# MotorControl.net
KiCad netlist of a schematic drawn in Altium Designer
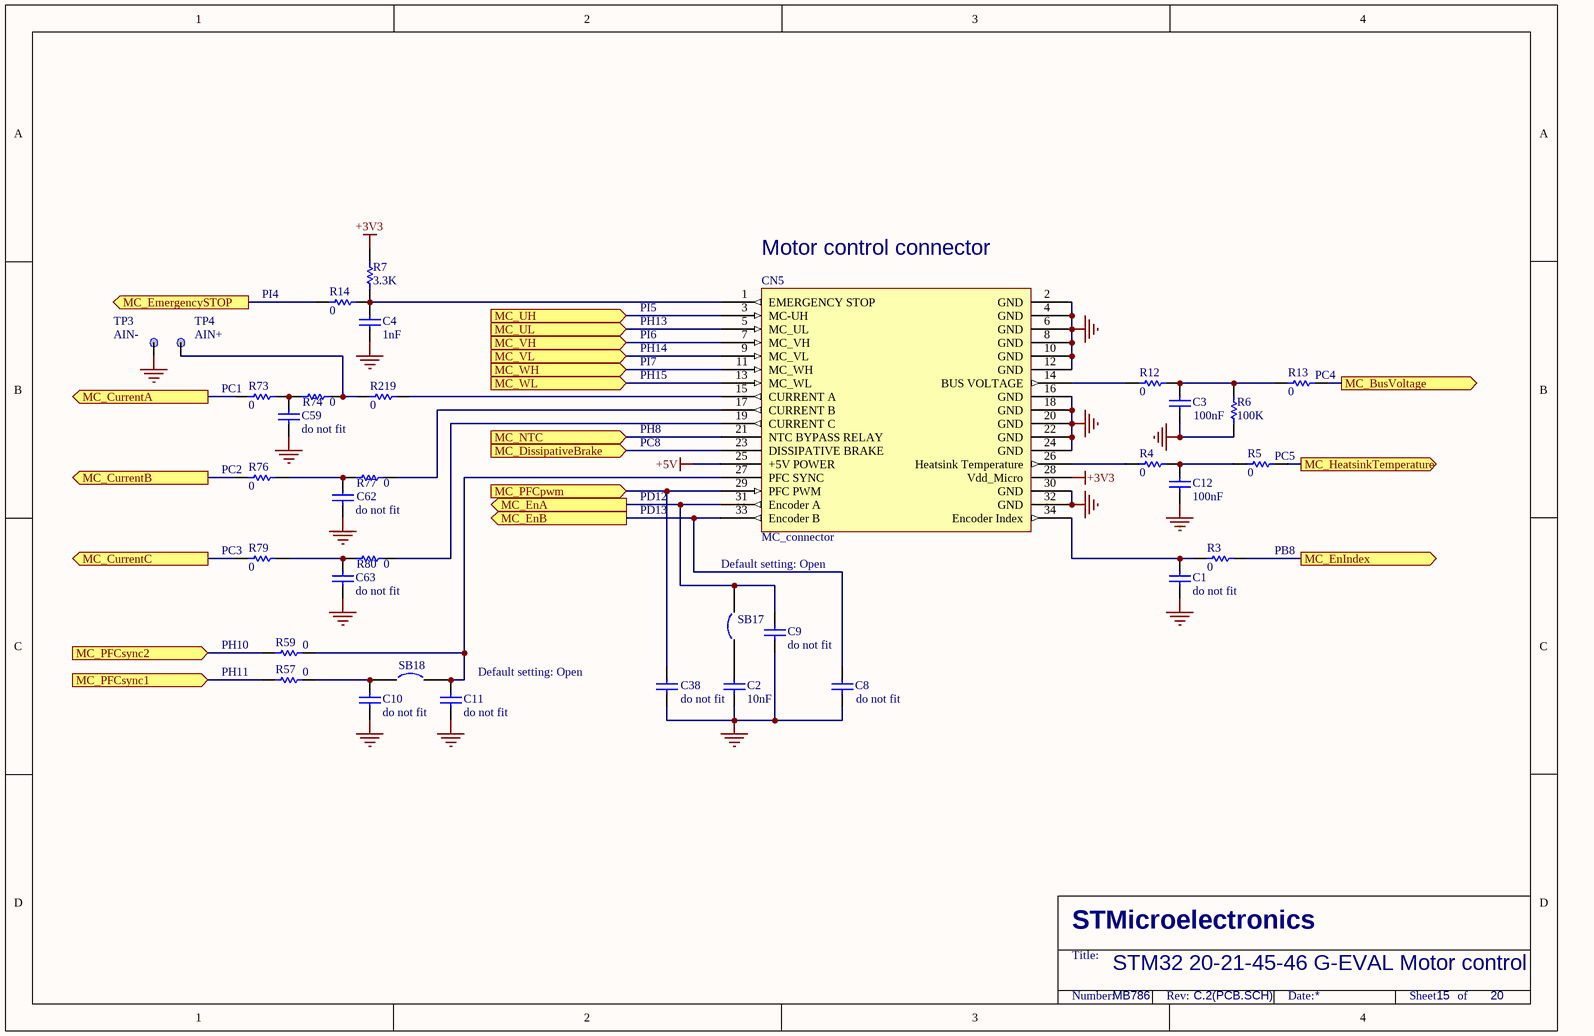
[diagram p0: MotorControl.SchDoc]

(export (version "E")
  (design (tool "Eeschema 10.0.6"))
  (components
    (comp (ref "C1")
      (value "do not fit")
      (footprint "0603C")
      (description "Capacitor")
      (fields (field (name "PUBLISHER") "Altium Limited"))
      (libsource (lib "Miscellaneous Devices") (part "cap"))
    )
    (comp (ref "C2")
      (value "10nF")
      (footprint "0402C")
      (description "Capacitor")
      (fields (field (name "PUBLISHER") "Altium Limited"))
      (libsource (lib "Miscellaneous Devices") (part "cap"))
    )
    (comp (ref "C3")
      (value "100nF")
      (footprint "0402C")
      (description "Capacitor")
      (fields (field (name "PUBLISHER") "Altium Limited"))
      (libsource (lib "Miscellaneous Devices") (part "cap"))
    )
    (comp (ref "C4")
      (value "1nF")
      (footprint "0603C")
      (description "Capacitor")
      (fields (field (name "PUBLISHER") "Altium Limited"))
      (libsource (lib "Miscellaneous Devices") (part "CAP"))
    )
    (comp (ref "C8")
      (value "do not fit")
      (footprint "0603C")
      (description "Capacitor")
      (fields (field (name "PUBLISHER") "Altium Limited"))
      (libsource (lib "Miscellaneous Devices") (part "cap"))
    )
    (comp (ref "C9")
      (value "do not fit")
      (footprint "0603C")
      (description "Capacitor")
      (fields (field (name "PUBLISHER") "Altium Limited"))
      (libsource (lib "Miscellaneous Devices") (part "cap"))
    )
    (comp (ref "C10")
      (value "do not fit")
      (footprint "0603C")
      (description "Capacitor")
      (fields (field (name "PUBLISHER") "Altium Limited"))
      (libsource (lib "Miscellaneous Devices") (part "cap"))
    )
    (comp (ref "C11")
      (value "do not fit")
      (footprint "0603C")
      (description "Capacitor")
      (fields (field (name "PUBLISHER") "Altium Limited"))
      (libsource (lib "Miscellaneous Devices") (part "cap"))
    )
    (comp (ref "C12")
      (value "100nF")
      (footprint "0402C")
      (description "Capacitor")
      (fields (field (name "PUBLISHER") "Altium Limited"))
      (libsource (lib "Miscellaneous Devices") (part "cap"))
    )
    (comp (ref "C38")
      (value "do not fit")
      (footprint "0603C")
      (description "Capacitor")
      (fields (field (name "PUBLISHER") "Altium Limited"))
      (libsource (lib "Miscellaneous Devices") (part "cap"))
    )
    (comp (ref "C59")
      (value "do not fit")
      (footprint "0603C")
      (description "Capacitor")
      (fields (field (name "PUBLISHER") "Altium Limited"))
      (libsource (lib "Miscellaneous Devices") (part "cap"))
    )
    (comp (ref "C62")
      (value "do not fit")
      (footprint "0603C")
      (description "Capacitor")
      (fields (field (name "PUBLISHER") "Altium Limited"))
      (libsource (lib "Miscellaneous Devices") (part "cap"))
    )
    (comp (ref "C63")
      (value "do not fit")
      (footprint "0603C")
      (description "Capacitor")
      (fields (field (name "PUBLISHER") "Altium Limited"))
      (libsource (lib "Miscellaneous Devices") (part "cap"))
    )
    (comp (ref "CN5")
      (value "MC_connector")
      (footprint "IDC34S")
      (libsource (lib "MB525") (part "MC_connector"))
    )
    (comp (ref "R3")
      (value "0")
      (footprint "0603R")
      (description "Resistor")
      (fields (field (name "PUBLISHER") "Altium Limited"))
      (libsource (lib "Miscellaneous Devices") (part "Res1"))
    )
    (comp (ref "R4")
      (value "0")
      (footprint "0603R")
      (description "Resistor")
      (fields (field (name "PUBLISHER") "Altium Limited"))
      (libsource (lib "Miscellaneous Devices") (part "Res1"))
    )
    (comp (ref "R5")
      (value "0")
      (footprint "0603R")
      (description "Resistor")
      (fields (field (name "PUBLISHER") "Altium Limited"))
      (libsource (lib "Miscellaneous Devices") (part "Res1"))
    )
    (comp (ref "R6")
      (value "100K")
      (footprint "0402R")
      (description "Resistor")
      (fields (field (name "PUBLISHER") "Altium Limited"))
      (libsource (lib "Miscellaneous Devices") (part "Res1"))
    )
    (comp (ref "R7")
      (value "3.3K")
      (footprint "0603R")
      (description "Resistor")
      (fields (field (name "PUBLISHER") "Altium Limited"))
      (libsource (lib "Miscellaneous Devices") (part "Res1"))
    )
    (comp (ref "R12")
      (value "0")
      (footprint "0603R")
      (description "Resistor")
      (fields (field (name "PUBLISHER") "Altium Limited"))
      (libsource (lib "Miscellaneous Devices") (part "Res1"))
    )
    (comp (ref "R13")
      (value "0")
      (footprint "0603R")
      (description "Resistor")
      (fields (field (name "PUBLISHER") "Altium Limited"))
      (libsource (lib "Miscellaneous Devices") (part "Res1"))
    )
    (comp (ref "R14")
      (value "0")
      (footprint "0603R")
      (description "Resistor")
      (fields (field (name "PUBLISHER") "Altium Limited"))
      (libsource (lib "Miscellaneous Devices") (part "Res1"))
    )
    (comp (ref "R57")
      (value "0")
      (footprint "0603R")
      (description "Resistor")
      (fields (field (name "PUBLISHER") "Altium Limited"))
      (libsource (lib "Miscellaneous Devices") (part "Res1"))
    )
    (comp (ref "R59")
      (value "0")
      (footprint "0603R")
      (description "Resistor")
      (fields (field (name "PUBLISHER") "Altium Limited"))
      (libsource (lib "Miscellaneous Devices") (part "Res1"))
    )
    (comp (ref "R73")
      (value "0")
      (footprint "0603R")
      (description "Resistor")
      (fields (field (name "PUBLISHER") "Altium Limited"))
      (libsource (lib "Miscellaneous Devices") (part "Res1"))
    )
    (comp (ref "R74")
      (value "0")
      (footprint "0603R")
      (description "Resistor")
      (fields (field (name "PUBLISHER") "Altium Limited"))
      (libsource (lib "Miscellaneous Devices") (part "Res1"))
    )
    (comp (ref "R76")
      (value "0")
      (footprint "0603R")
      (description "Resistor")
      (fields (field (name "PUBLISHER") "Altium Limited"))
      (libsource (lib "Miscellaneous Devices") (part "Res1"))
    )
    (comp (ref "R77")
      (value "0")
      (footprint "0603R")
      (description "Resistor")
      (fields (field (name "PUBLISHER") "Altium Limited"))
      (libsource (lib "Miscellaneous Devices") (part "Res1"))
    )
    (comp (ref "R79")
      (value "0")
      (footprint "0603R")
      (description "Resistor")
      (fields (field (name "PUBLISHER") "Altium Limited"))
      (libsource (lib "Miscellaneous Devices") (part "Res1"))
    )
    (comp (ref "R80")
      (value "0")
      (footprint "0603R")
      (description "Resistor")
      (fields (field (name "PUBLISHER") "Altium Limited"))
      (libsource (lib "Miscellaneous Devices") (part "Res1"))
    )
    (comp (ref "R219")
      (value "0")
      (footprint "0603R")
      (description "Resistor")
      (fields (field (name "PUBLISHER") "Altium Limited"))
      (libsource (lib "Miscellaneous Devices") (part "Res1"))
    )
    (comp (ref "SB17")
      (value "~")
      (footprint "JP2_SMD")
      (description "Circuit Breaker")
      (fields (field (name "PUBLISHER") "Altium Limited"))
      (libsource (lib "Miscellaneous Devices") (part "Circuit Breaker"))
    )
    (comp (ref "SB18")
      (value "~")
      (footprint "JP2_SMD")
      (description "Circuit Breaker")
      (fields (field (name "PUBLISHER") "Altium Limited"))
      (libsource (lib "Miscellaneous Devices") (part "Circuit Breaker"))
    )
    (comp (ref "TP3") (value "AIN-") (footprint "TP") (libsource (lib "*") (part "TP")))
    (comp (ref "TP4") (value "AIN+") (footprint "TP") (libsource (lib "*") (part "TP")))
  )
  (nets
    (net (code "1") (name "+3V3") (class "Default")
      (node (ref "CN5") (pin "28") (pinfunction "Vdd_Micro_28") (pintype "power_in"))
      (node (ref "R7") (pin "2") (pinfunction "2_2") (pintype "passive"))
    )
    (net (code "2") (name "+5V") (class "Default")
      (node (ref "CN5") (pin "25") (pinfunction "+5V_POWER_25") (pintype "power_in"))
    )
    (net (code "3") (name "/MC_BusVoltage") (class "Default")
      (node (ref "R13") (pin "2") (pinfunction "2_2") (pintype "passive"))
    )
    (net (code "4") (name "/MC_CurrentA") (class "Default")
      (node (ref "R73") (pin "1") (pinfunction "1_1") (pintype "passive"))
    )
    (net (code "5") (name "/MC_CurrentB") (class "Default")
      (node (ref "R76") (pin "1") (pinfunction "1_1") (pintype "passive"))
    )
    (net (code "6") (name "/MC_CurrentC") (class "Default")
      (node (ref "R79") (pin "1") (pinfunction "1_1") (pintype "passive"))
    )
    (net (code "7") (name "/MC_DissipativeBrake") (class "Default")
      (node (ref "CN5") (pin "23") (pinfunction "DISSIPATIVE_BRAKE_23") (pintype "passive"))
    )
    (net (code "8") (name "/MC_EmergencySTOP") (class "Default")
      (node (ref "R14") (pin "2") (pinfunction "2_2") (pintype "passive"))
    )
    (net (code "9") (name "/MC_EnA") (class "Default")
      (node (ref "C9") (pin "2") (pinfunction "2_2") (pintype "passive"))
      (node (ref "CN5") (pin "31") (pinfunction "Encoder_A_31") (pintype "output"))
      (node (ref "SB17") (pin "2") (pinfunction "2_2") (pintype "passive"))
    )
    (net (code "10") (name "/MC_EnB") (class "Default")
      (node (ref "C8") (pin "2") (pinfunction "2_2") (pintype "passive"))
      (node (ref "CN5") (pin "33") (pinfunction "Encoder_B_33") (pintype "output"))
    )
    (net (code "11") (name "/MC_EnIndex") (class "Default")
      (node (ref "R3") (pin "2") (pinfunction "2_2") (pintype "passive"))
    )
    (net (code "12") (name "/MC_HeatsinkTemperature") (class "Default")
      (node (ref "R5") (pin "2") (pinfunction "2_2") (pintype "passive"))
    )
    (net (code "13") (name "/MC_NTC") (class "Default")
      (node (ref "CN5") (pin "21") (pinfunction "NTC_BYPASS_RELAY_21") (pintype "passive"))
    )
    (net (code "14") (name "/MC_PFCpwm") (class "Default")
      (node (ref "C38") (pin "2") (pinfunction "2_2") (pintype "passive"))
      (node (ref "CN5") (pin "29") (pinfunction "PFC_PWM_29") (pintype "input"))
    )
    (net (code "15") (name "/MC_PFCsync1") (class "Default")
      (node (ref "R57") (pin "1") (pinfunction "1_1") (pintype "passive"))
    )
    (net (code "16") (name "/MC_PFCsync2") (class "Default")
      (node (ref "R59") (pin "1") (pinfunction "1_1") (pintype "passive"))
    )
    (net (code "17") (name "/MC_UH") (class "Default")
      (node (ref "CN5") (pin "3") (pinfunction "MC-UH_3") (pintype "input"))
    )
    (net (code "18") (name "/MC_UL") (class "Default")
      (node (ref "CN5") (pin "5") (pinfunction "MC_UL_5") (pintype "input"))
    )
    (net (code "19") (name "/MC_VH") (class "Default")
      (node (ref "CN5") (pin "7") (pinfunction "MC_VH_7") (pintype "input"))
    )
    (net (code "20") (name "/MC_VL") (class "Default")
      (node (ref "CN5") (pin "9") (pinfunction "MC_VL_9") (pintype "input"))
    )
    (net (code "21") (name "/MC_WH") (class "Default")
      (node (ref "CN5") (pin "11") (pinfunction "MC_WH_11") (pintype "input"))
    )
    (net (code "22") (name "/MC_WL") (class "Default")
      (node (ref "CN5") (pin "13") (pinfunction "MC_WL_13") (pintype "input"))
    )
    (net (code "23") (name "GND") (class "Default")
      (node (ref "C1") (pin "1") (pinfunction "1_1") (pintype "passive"))
      (node (ref "C10") (pin "1") (pinfunction "1_1") (pintype "passive"))
      (node (ref "C11") (pin "1") (pinfunction "1_1") (pintype "passive"))
      (node (ref "C12") (pin "1") (pinfunction "1_1") (pintype "passive"))
      (node (ref "C2") (pin "1") (pinfunction "1_1") (pintype "passive"))
      (node (ref "C3") (pin "1") (pinfunction "1_1") (pintype "passive"))
      (node (ref "C38") (pin "1") (pinfunction "1_1") (pintype "passive"))
      (node (ref "C4") (pin "1") (pinfunction "1_1") (pintype "passive"))
      (node (ref "C59") (pin "1") (pinfunction "1_1") (pintype "passive"))
      (node (ref "C62") (pin "1") (pinfunction "1_1") (pintype "passive"))
      (node (ref "C63") (pin "1") (pinfunction "1_1") (pintype "passive"))
      (node (ref "C8") (pin "1") (pinfunction "1_1") (pintype "passive"))
      (node (ref "C9") (pin "1") (pinfunction "1_1") (pintype "passive"))
      (node (ref "CN5") (pin "10") (pinfunction "GND_10") (pintype "power_in"))
      (node (ref "CN5") (pin "12") (pinfunction "GND_12") (pintype "power_in"))
      (node (ref "CN5") (pin "16") (pinfunction "GND_16") (pintype "power_in"))
      (node (ref "CN5") (pin "18") (pinfunction "GND_18") (pintype "power_in"))
      (node (ref "CN5") (pin "2") (pinfunction "GND_2") (pintype "power_in"))
      (node (ref "CN5") (pin "20") (pinfunction "GND_20") (pintype "power_in"))
      (node (ref "CN5") (pin "22") (pinfunction "GND_22") (pintype "power_in"))
      (node (ref "CN5") (pin "24") (pinfunction "GND_24") (pintype "power_in"))
      (node (ref "CN5") (pin "30") (pinfunction "GND_30") (pintype "power_in"))
      (node (ref "CN5") (pin "32") (pinfunction "GND_32") (pintype "power_in"))
      (node (ref "CN5") (pin "4") (pinfunction "GND_4") (pintype "power_in"))
      (node (ref "CN5") (pin "6") (pinfunction "GND_6") (pintype "power_in"))
      (node (ref "CN5") (pin "8") (pinfunction "GND_8") (pintype "power_in"))
      (node (ref "R6") (pin "1") (pinfunction "1_1") (pintype "passive"))
      (node (ref "TP3") (pin "1") (pinfunction "1_1") (pintype "passive"))
    )
    (net (code "24") (name "Net-(C2-Pad2)") (class "Default")
      (node (ref "C2") (pin "2") (pinfunction "2_2") (pintype "passive"))
      (node (ref "SB17") (pin "1") (pinfunction "1_1") (pintype "passive"))
    )
    (net (code "25") (name "Net-(C3-Pad2)") (class "Default")
      (node (ref "C3") (pin "2") (pinfunction "2_2") (pintype "passive"))
      (node (ref "R12") (pin "2") (pinfunction "2_2") (pintype "passive"))
      (node (ref "R13") (pin "1") (pinfunction "1_1") (pintype "passive"))
      (node (ref "R6") (pin "2") (pinfunction "2_2") (pintype "passive"))
    )
    (net (code "26") (name "Net-(C10-Pad2)") (class "Default")
      (node (ref "C10") (pin "2") (pinfunction "2_2") (pintype "passive"))
      (node (ref "R57") (pin "2") (pinfunction "2_2") (pintype "passive"))
      (node (ref "SB18") (pin "1") (pinfunction "1_1") (pintype "passive"))
    )
    (net (code "27") (name "Net-(C12-Pad2)") (class "Default")
      (node (ref "C12") (pin "2") (pinfunction "2_2") (pintype "passive"))
      (node (ref "R4") (pin "2") (pinfunction "2_2") (pintype "passive"))
      (node (ref "R5") (pin "1") (pinfunction "1_1") (pintype "passive"))
    )
    (net (code "28") (name "Net-(C59-Pad2)") (class "Default")
      (node (ref "C59") (pin "2") (pinfunction "2_2") (pintype "passive"))
      (node (ref "R73") (pin "2") (pinfunction "2_2") (pintype "passive"))
      (node (ref "R74") (pin "1") (pinfunction "1_1") (pintype "passive"))
    )
    (net (code "29") (name "Net-(C62-Pad2)") (class "Default")
      (node (ref "C62") (pin "2") (pinfunction "2_2") (pintype "passive"))
      (node (ref "R76") (pin "2") (pinfunction "2_2") (pintype "passive"))
      (node (ref "R77") (pin "1") (pinfunction "1_1") (pintype "passive"))
    )
    (net (code "30") (name "Net-(C63-Pad2)") (class "Default")
      (node (ref "C63") (pin "2") (pinfunction "2_2") (pintype "passive"))
      (node (ref "R79") (pin "2") (pinfunction "2_2") (pintype "passive"))
      (node (ref "R80") (pin "1") (pinfunction "1_1") (pintype "passive"))
    )
    (net (code "31") (name "Net-(CN5-BUS_VOLTAGE)") (class "Default")
      (node (ref "CN5") (pin "14") (pinfunction "BUS_VOLTAGE_14") (pintype "output"))
      (node (ref "R12") (pin "1") (pinfunction "1_1") (pintype "passive"))
    )
    (net (code "32") (name "Net-(CN5-CURRENT_A)") (class "Default")
      (node (ref "CN5") (pin "15") (pinfunction "CURRENT_A_15") (pintype "output"))
      (node (ref "R219") (pin "1") (pinfunction "1_1") (pintype "passive"))
    )
    (net (code "33") (name "Net-(CN5-CURRENT_B)") (class "Default")
      (node (ref "CN5") (pin "17") (pinfunction "CURRENT_B_17") (pintype "output"))
      (node (ref "R77") (pin "2") (pinfunction "2_2") (pintype "passive"))
    )
    (net (code "34") (name "Net-(CN5-CURRENT_C)") (class "Default")
      (node (ref "CN5") (pin "19") (pinfunction "CURRENT_C_19") (pintype "output"))
      (node (ref "R80") (pin "2") (pinfunction "2_2") (pintype "passive"))
    )
    (net (code "35") (name "Net-(CN5-EMERGENCY_STOP)") (class "Default")
      (node (ref "C4") (pin "2") (pinfunction "2_2") (pintype "passive"))
      (node (ref "CN5") (pin "1") (pinfunction "EMERGENCY_STOP_1") (pintype "output"))
      (node (ref "R14") (pin "1") (pinfunction "1_1") (pintype "passive"))
      (node (ref "R7") (pin "1") (pinfunction "1_1") (pintype "passive"))
    )
    (net (code "36") (name "Net-(CN5-Encoder_Index)") (class "Default")
      (node (ref "C1") (pin "2") (pinfunction "2_2") (pintype "passive"))
      (node (ref "CN5") (pin "34") (pinfunction "Encoder_Index_34") (pintype "output"))
      (node (ref "R3") (pin "1") (pinfunction "1_1") (pintype "passive"))
    )
    (net (code "37") (name "Net-(CN5-Heatsink_Temperature)") (class "Default")
      (node (ref "CN5") (pin "26") (pinfunction "Heatsink_Temperature_26") (pintype "output"))
      (node (ref "R4") (pin "1") (pinfunction "1_1") (pintype "passive"))
    )
    (net (code "38") (name "Net-(CN5-PFC_SYNC)") (class "Default")
      (node (ref "C11") (pin "2") (pinfunction "2_2") (pintype "passive"))
      (node (ref "CN5") (pin "27") (pinfunction "PFC_SYNC_27") (pintype "passive"))
      (node (ref "R59") (pin "2") (pinfunction "2_2") (pintype "passive"))
      (node (ref "SB18") (pin "2") (pinfunction "2_2") (pintype "passive"))
    )
    (net (code "39") (name "Net-(R219-Pad2)") (class "Default")
      (node (ref "R219") (pin "2") (pinfunction "2_2") (pintype "passive"))
      (node (ref "R74") (pin "2") (pinfunction "2_2") (pintype "passive"))
      (node (ref "TP4") (pin "1") (pinfunction "1_1") (pintype "passive"))
    )
  )
)
